# EM8500.net
KiCad netlist of a schematic drawn in Altium Designer
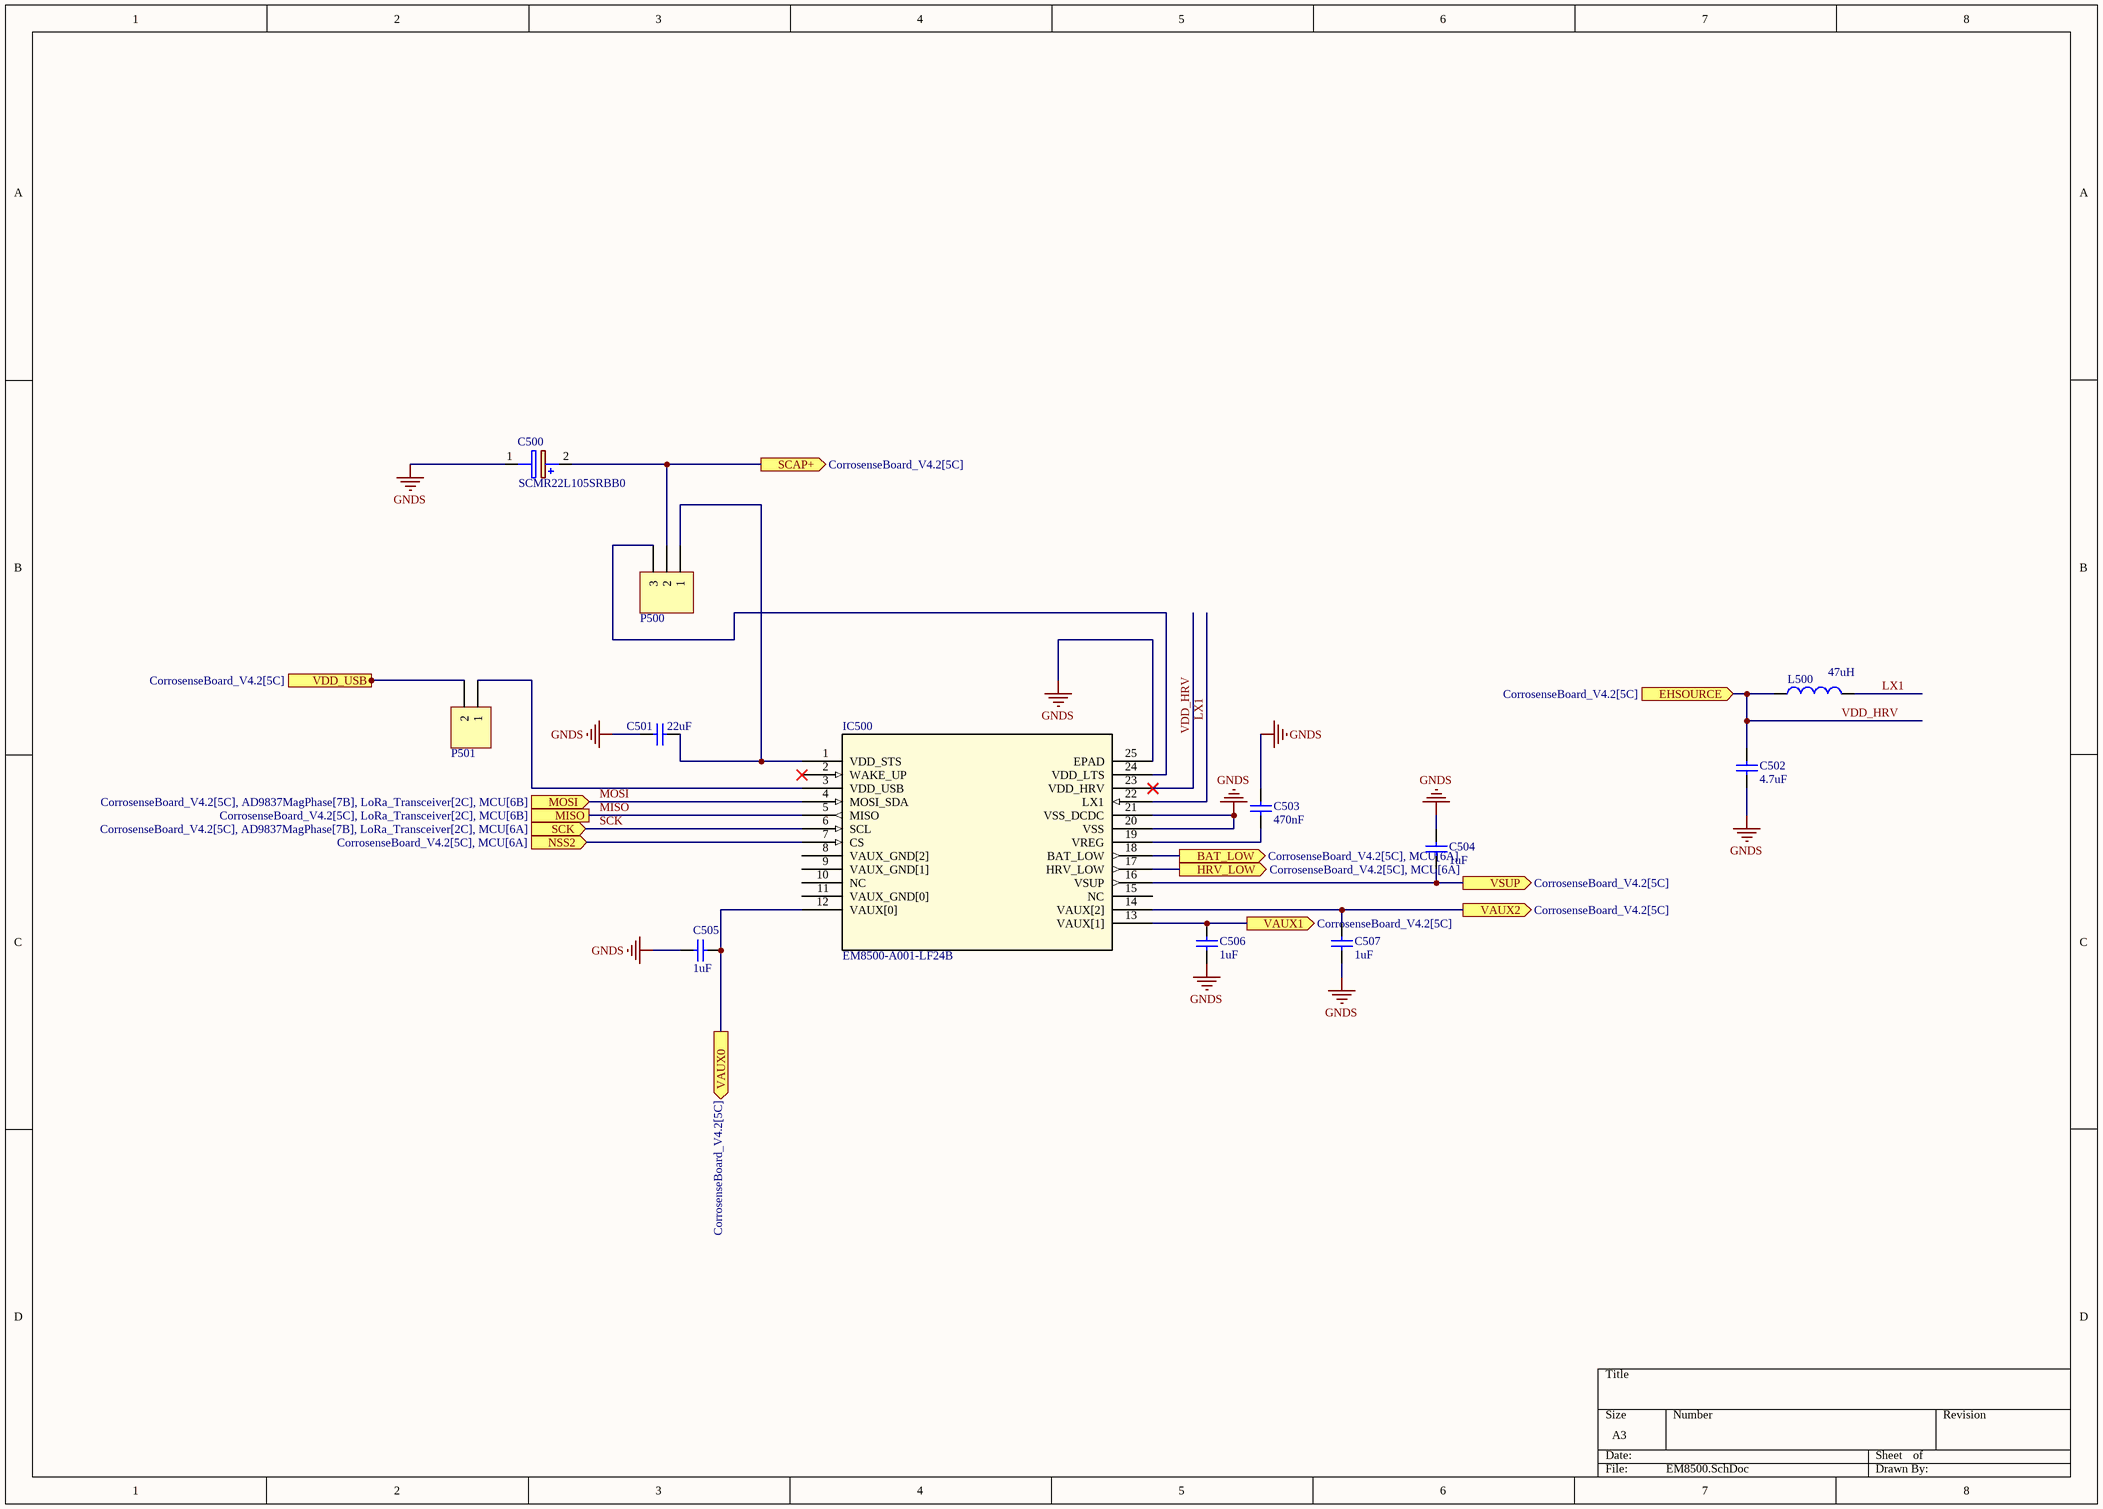
[diagram p0: EM8500.SchDoc]

(export (version "E")
  (design (tool "Eeschema 10.0.6"))
  (components
    (comp (ref "C500")
      (value "SCMR22L105SRBB0")
      (footprint "SCMR22L105SRBB0")
      (description "Capacitor Polarised")
      (fields (field (name "MOUSER PART NUMBER") "581-SCMR22L105SRBB0") (field (name "TOLERANCE") "±10%"))
      (libsource (lib "*") (part "SCMR22L105SRBB0"))
    )
    (comp (ref "C501")
      (value "22uF")
      (footprint "1608[0603]")
      (description "CAP CER 25V X7R 0603")
      (fields (field (name "TOLERANCE") "±10%") (field (name "MANUFACTURER") "Murata Electronics"))
      (libsource (lib "Miscellaneous Devices") (part "Cap"))
    )
    (comp (ref "C502")
      (value "4.7uF")
      (footprint "1608[0603]")
      (description "CAP CER 25V X7R 0603")
      (fields (field (name "TOLERANCE") "±10%") (field (name "MANUFACTURER") "Murata Electronics"))
      (libsource (lib "Miscellaneous Devices") (part "Cap"))
    )
    (comp (ref "C503")
      (value "470nF")
      (footprint "1608[0603]")
      (description "CAP CER 25V X7R 0603")
      (fields (field (name "TOLERANCE") "±10%") (field (name "MANUFACTURER") "Murata Electronics"))
      (libsource (lib "Miscellaneous Devices") (part "Cap"))
    )
    (comp (ref "C504")
      (value "1uF")
      (footprint "1608[0603]")
      (description "CAP CER 25V X7R 0603")
      (fields (field (name "TOLERANCE") "±10%") (field (name "MANUFACTURER") "Murata Electronics"))
      (libsource (lib "Miscellaneous Devices") (part "Cap"))
    )
    (comp (ref "C505")
      (value "1uF")
      (footprint "1608[0603]")
      (description "CAP CER 25V X7R 0603")
      (fields (field (name "TOLERANCE") "±10%") (field (name "MANUFACTURER") "Murata Electronics"))
      (libsource (lib "Miscellaneous Devices") (part "Cap"))
    )
    (comp (ref "C506")
      (value "1uF")
      (footprint "1608[0603]")
      (description "CAP CER 25V X7R 0603")
      (fields (field (name "TOLERANCE") "±10%") (field (name "MANUFACTURER") "Murata Electronics"))
      (libsource (lib "Miscellaneous Devices") (part "Cap"))
    )
    (comp (ref "C507")
      (value "1uF")
      (footprint "1608[0603]")
      (description "CAP CER 25V X7R 0603")
      (fields (field (name "TOLERANCE") "±10%") (field (name "MANUFACTURER") "Murata Electronics"))
      (libsource (lib "Miscellaneous Devices") (part "Cap"))
    )
    (comp (ref "IC500")
      (value "EM8500-A001-LF24B")
      (footprint "QFN24_4X4_MAR")
      (description "No Description Available")
      (fields
        (field (name "MANUFACTURER") "EM Microelectronic-Marin")
        (field (name "MPN") "EM8500-A001-LF24B+")
      )
      (libsource (lib "EM8500-A001-LF24B") (part "EM8500-A001-LF24B"))
    )
    (comp (ref "L500")
      (value "47uH")
      (footprint "C0805")
      (description "Inductor")
      (fields
        (field (name "MANUFACTURER") "TAIYO YUDEN")
        (field (name "MPN") "BRL2012T470M")
        (field (name "PUBLISHER") "Altium Limited")
      )
      (libsource (lib "Miscellaneous Devices") (part "Inductor"))
    )
    (comp (ref "P500")
      (value "Header, 3-Pin")
      (footprint "HDR1X3")
      (fields
        (field (name "MANUFACTURER") "Wurth Elektronik")
        (field (name "MPN") "61300311121")
        (field (name "PUBLISHER") "Altium Limited")
      )
      (libsource (lib "Miscellaneous Connectors") (part "Header 3"))
    )
    (comp (ref "P501")
      (value "Header, 2-Pin")
      (footprint "HDR1X2")
      (fields
        (field (name "MANUFACTURER") "Wurth Elektronik")
        (field (name "MPN") "61300211121")
        (field (name "PUBLISHER") "Altium Limited")
      )
      (libsource (lib "Miscellaneous Connectors") (part "Header 2"))
    )
  )
  (nets
    (net (code "1") (name "/BAT_LOW") (class "Default")
      (node (ref "IC500") (pin "18") (pinfunction "BAT_LOW_18") (pintype "output"))
    )
    (net (code "2") (name "/HRV_LOW") (class "Default")
      (node (ref "IC500") (pin "17") (pinfunction "HRV_LOW_17") (pintype "output"))
    )
    (net (code "3") (name "/LX1") (class "Default")
      (node (ref "IC500") (pin "22") (pinfunction "LX1_22") (pintype "input"))
      (node (ref "L500") (pin "2") (pinfunction "2_2") (pintype "passive"))
    )
    (net (code "4") (name "/MISO") (class "Default")
      (node (ref "IC500") (pin "5") (pinfunction "MISO_5") (pintype "output"))
    )
    (net (code "5") (name "/MOSI") (class "Default")
      (node (ref "IC500") (pin "4") (pinfunction "MOSI_SDA_4") (pintype "input"))
    )
    (net (code "6") (name "/NSS2") (class "Default")
      (node (ref "IC500") (pin "7") (pinfunction "CS_7") (pintype "input"))
    )
    (net (code "7") (name "/SCAP+") (class "Default")
      (node (ref "C500") (pin "2") (pinfunction "+_2") (pintype "passive"))
      (node (ref "P500") (pin "2") (pinfunction "2_2") (pintype "passive"))
    )
    (net (code "8") (name "/SCK") (class "Default")
      (node (ref "IC500") (pin "6") (pinfunction "SCL_6") (pintype "input"))
    )
    (net (code "9") (name "/VAUX0") (class "Default")
      (node (ref "C505") (pin "2") (pinfunction "2_2") (pintype "passive"))
      (node (ref "IC500") (pin "12") (pinfunction "VAUX[0]_12") (pintype "power_in"))
    )
    (net (code "10") (name "/VAUX1") (class "Default")
      (node (ref "C506") (pin "2") (pinfunction "2_2") (pintype "passive"))
      (node (ref "IC500") (pin "13") (pinfunction "VAUX[1]_13") (pintype "power_in"))
    )
    (net (code "11") (name "/VAUX2") (class "Default")
      (node (ref "C507") (pin "2") (pinfunction "2_2") (pintype "passive"))
      (node (ref "IC500") (pin "14") (pinfunction "VAUX[2]_14") (pintype "power_in"))
    )
    (net (code "12") (name "/VDD_HRV") (class "Default")
      (node (ref "C502") (pin "2") (pinfunction "2_2") (pintype "passive"))
      (node (ref "IC500") (pin "23") (pinfunction "VDD_HRV_23") (pintype "power_in"))
      (node (ref "L500") (pin "1") (pinfunction "1_1") (pintype "passive"))
    )
    (net (code "13") (name "/VDD_USB") (class "Default")
      (node (ref "P501") (pin "2") (pinfunction "2_2") (pintype "passive"))
    )
    (net (code "14") (name "/VSUP") (class "Default")
      (node (ref "C504") (pin "1") (pinfunction "1_1") (pintype "passive"))
      (node (ref "IC500") (pin "16") (pinfunction "VSUP_16") (pintype "output"))
    )
    (net (code "15") (name "GNDS") (class "Default")
      (node (ref "C500") (pin "1") (pinfunction "-_1") (pintype "passive"))
      (node (ref "C501") (pin "1") (pinfunction "1_1") (pintype "passive"))
      (node (ref "C502") (pin "1") (pinfunction "1_1") (pintype "passive"))
      (node (ref "C503") (pin "1") (pinfunction "1_1") (pintype "passive"))
      (node (ref "C504") (pin "2") (pinfunction "2_2") (pintype "passive"))
      (node (ref "C505") (pin "1") (pinfunction "1_1") (pintype "passive"))
      (node (ref "C506") (pin "1") (pinfunction "1_1") (pintype "passive"))
      (node (ref "C507") (pin "1") (pinfunction "1_1") (pintype "passive"))
      (node (ref "IC500") (pin "20") (pinfunction "VSS_20") (pintype "power_in"))
      (node (ref "IC500") (pin "21") (pinfunction "VSS_DCDC_21") (pintype "power_in"))
      (node (ref "IC500") (pin "25") (pinfunction "EPAD_25") (pintype "passive"))
    )
    (net (code "16") (name "Net-(IC500-VDD_LTS)") (class "Default")
      (node (ref "IC500") (pin "24") (pinfunction "VDD_LTS_24") (pintype "power_in"))
      (node (ref "P500") (pin "3") (pinfunction "3_3") (pintype "passive"))
    )
    (net (code "17") (name "Net-(IC500-VDD_STS)") (class "Default")
      (node (ref "C501") (pin "2") (pinfunction "2_2") (pintype "passive"))
      (node (ref "IC500") (pin "1") (pinfunction "VDD_STS_1") (pintype "power_in"))
      (node (ref "P500") (pin "1") (pinfunction "1_1") (pintype "passive"))
    )
    (net (code "18") (name "Net-(IC500-VDD_USB)") (class "Default")
      (node (ref "IC500") (pin "3") (pinfunction "VDD_USB_3") (pintype "power_in"))
      (node (ref "P501") (pin "1") (pinfunction "1_1") (pintype "passive"))
    )
    (net (code "19") (name "Net-(IC500-VREG)") (class "Default")
      (node (ref "C503") (pin "2") (pinfunction "2_2") (pintype "passive"))
      (node (ref "IC500") (pin "19") (pinfunction "VREG_19") (pintype "power_in"))
    )
    (net (code "20") (name "unconnected-(IC500-NC-Pad10)") (class "Default")
      (node (ref "IC500") (pin "10") (pinfunction "NC_10") (pintype "passive"))
    )
    (net (code "21") (name "unconnected-(IC500-NC-Pad15)") (class "Default")
      (node (ref "IC500") (pin "15") (pinfunction "NC_15") (pintype "passive"))
    )
    (net (code "22") (name "unconnected-(IC500-VAUX_GND[0]-Pad11)") (class "Default")
      (node (ref "IC500") (pin "11") (pinfunction "VAUX_GND[0]_11") (pintype "power_in"))
    )
    (net (code "23") (name "unconnected-(IC500-VAUX_GND[1]-Pad9)") (class "Default")
      (node (ref "IC500") (pin "9") (pinfunction "VAUX_GND[1]_9") (pintype "power_in"))
    )
    (net (code "24") (name "unconnected-(IC500-VAUX_GND[2]-Pad8)") (class "Default")
      (node (ref "IC500") (pin "8") (pinfunction "VAUX_GND[2]_8") (pintype "power_in"))
    )
    (net (code "25") (name "unconnected-(IC500-WAKE_UP-Pad2)") (class "Default")
      (node (ref "IC500") (pin "2") (pinfunction "WAKE_UP_2") (pintype "input+no_connect"))
    )
  )
)
